# brain.net
KiCad netlist of a schematic drawn in EAGLE
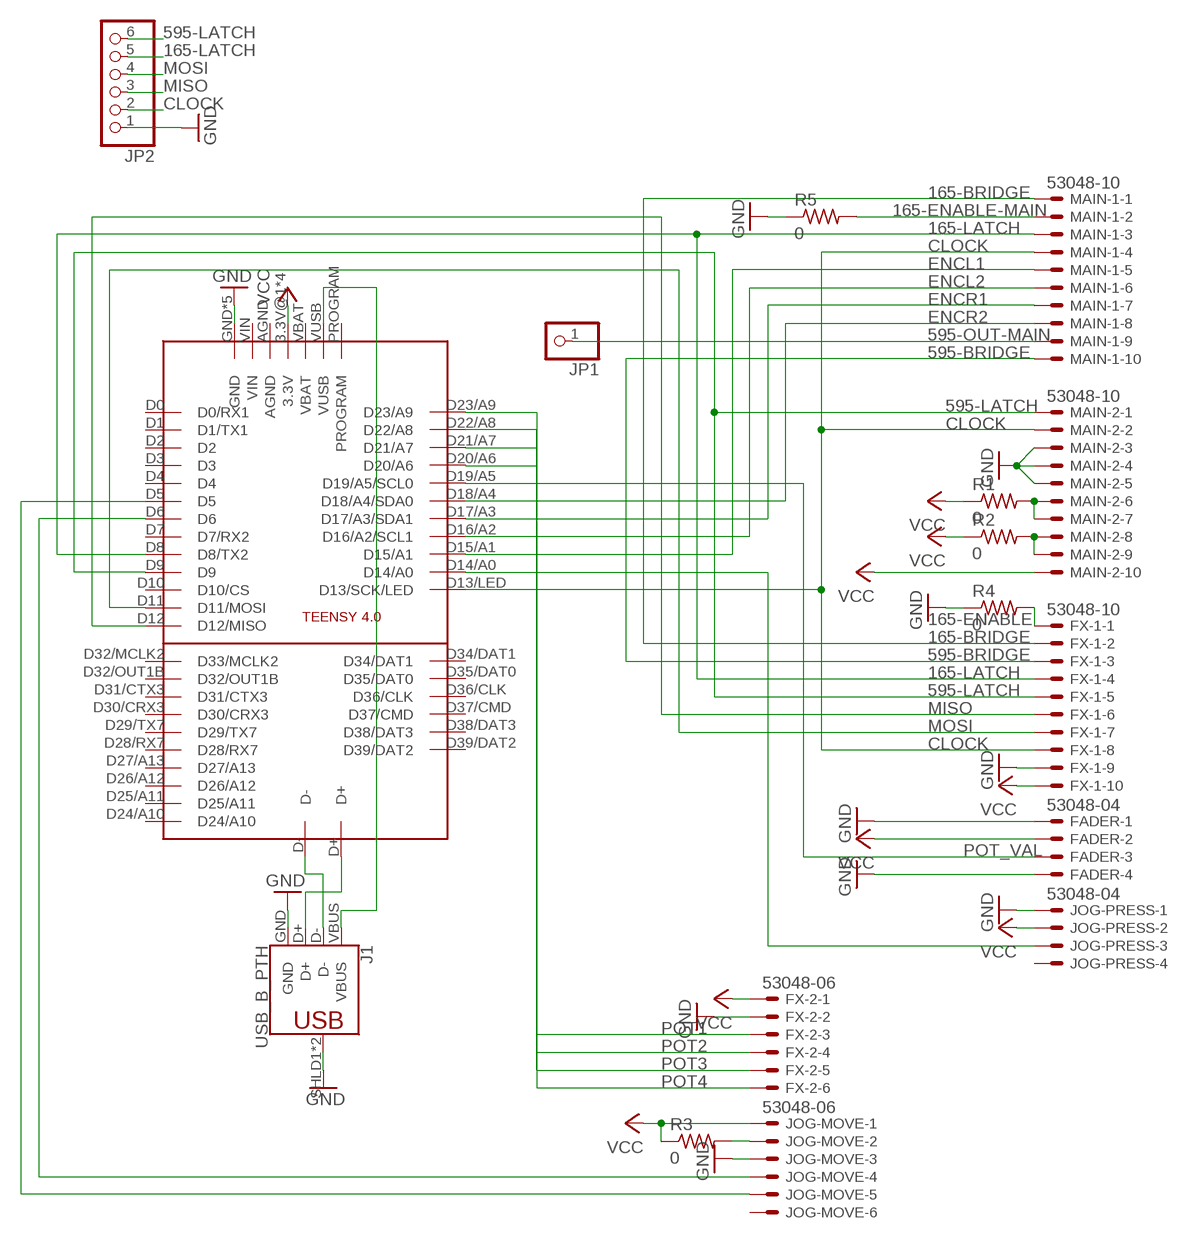
[diagram p0: schematic, sheet 1]

(export (version "E")
  (design (tool "Eeschema 10.0.6"))
  (components
    (comp (ref "FADER")
      (value "53048-04")
      (footprint "eagle-import:53048-04")
      (fields (field (name "MF") "MOLEX") (field (name "MPN") "53048-0410"))
      (libsource (lib "eagle-import") (part "53?-04048"))
    )
    (comp (ref "FX-1")
      (value "53048-10")
      (footprint "eagle-import:53048-10")
      (fields (field (name "MF") "MOLEX") (field (name "MPN") "53048-1010"))
      (libsource (lib "eagle-import") (part "53?-10048"))
    )
    (comp (ref "FX-2")
      (value "53048-06")
      (footprint "eagle-import:53048-06")
      (fields (field (name "MF") "WALDOM/MOLEX") (field (name "MPN") "53048-0610"))
      (libsource (lib "eagle-import") (part "53?-06048"))
    )
    (comp (ref "J1")
      (value "USB_B_PTH")
      (footprint "eagle-import:USB-B-PTH")
      (libsource (lib "eagle-import") (part "USB_B_PTH"))
    )
    (comp (ref "JOG-MOVE")
      (value "53048-06")
      (footprint "eagle-import:53048-06")
      (fields (field (name "MF") "WALDOM/MOLEX") (field (name "MPN") "53048-0610"))
      (libsource (lib "eagle-import") (part "53?-06048"))
    )
    (comp (ref "JOG-PRESS")
      (value "53048-04")
      (footprint "eagle-import:53048-04")
      (fields (field (name "MF") "MOLEX") (field (name "MPN") "53048-0410"))
      (libsource (lib "eagle-import") (part "53?-04048"))
    )
    (comp (ref "JP1")
      (value "PINHD-1X1")
      (footprint "eagle-import:1X01")
      (libsource (lib "eagle-import") (part "PINHD-1X1"))
    )
    (comp (ref "JP2")
      (value "PINHD-1X6")
      (footprint "eagle-import:1X06")
      (libsource (lib "eagle-import") (part "PINHD-1X6"))
    )
    (comp (ref "MAIN-1")
      (value "53048-10")
      (footprint "eagle-import:53048-10")
      (fields (field (name "MF") "MOLEX") (field (name "MPN") "53048-1010"))
      (libsource (lib "eagle-import") (part "53?-10048"))
    )
    (comp (ref "MAIN-2")
      (value "53048-10")
      (footprint "eagle-import:53048-10")
      (fields (field (name "MF") "MOLEX") (field (name "MPN") "53048-1010"))
      (libsource (lib "eagle-import") (part "53?-10048"))
    )
    (comp (ref "R1")
      (value "0")
      (footprint "eagle-import:R1206")
      (libsource (lib "eagle-import") (part "R-US_R1206"))
    )
    (comp (ref "R2")
      (value "0")
      (footprint "eagle-import:R1206")
      (libsource (lib "eagle-import") (part "R-US_R1206"))
    )
    (comp (ref "R3")
      (value "0")
      (footprint "eagle-import:R1206")
      (libsource (lib "eagle-import") (part "R-US_R1206"))
    )
    (comp (ref "R4")
      (value "0")
      (footprint "eagle-import:R1206")
      (libsource (lib "eagle-import") (part "R-US_R1206"))
    )
    (comp (ref "R5")
      (value "0")
      (footprint "eagle-import:R1206")
      (libsource (lib "eagle-import") (part "R-US_R1206"))
    )
    (comp (ref "U$1")
      (value "TEENSY-4.0-FULL-BRAKE-PADS")
      (footprint "eagle-import:TEENSY-4.0-FULL-BRAKE-PADS")
      (libsource (lib "eagle-import") (part "TEENSY-4.0-FULL-BRAKE-PADS"))
    )
  )
  (nets
    (net (code "1") (name "/165-BRIDGE") (class "Default")
      (node (ref "FX-1") (pin "2") (pinfunction "S_2") (pintype "passive"))
      (node (ref "MAIN-1") (pin "1") (pinfunction "S_1") (pintype "passive"))
    )
    (net (code "2") (name "/165-ENABLE") (class "Default")
      (node (ref "FX-1") (pin "1") (pinfunction "S_1") (pintype "passive"))
      (node (ref "R4") (pin "2") (pinfunction "2_2") (pintype "passive"))
    )
    (net (code "3") (name "/165-ENABLE-MAIN") (class "Default")
      (node (ref "MAIN-1") (pin "2") (pinfunction "S_2") (pintype "passive"))
      (node (ref "R5") (pin "2") (pinfunction "2_2") (pintype "passive"))
    )
    (net (code "4") (name "/165-LATCH") (class "Default")
      (node (ref "FX-1") (pin "4") (pinfunction "S_4") (pintype "passive"))
      (node (ref "JP2") (pin "5") (pinfunction "5_5") (pintype "passive"))
      (node (ref "MAIN-1") (pin "3") (pinfunction "S_3") (pintype "passive"))
      (node (ref "U$1") (pin "D8") (pinfunction "D8/TX2_D8") (pintype "bidirectional"))
    )
    (net (code "5") (name "/595-BRIDGE") (class "Default")
      (node (ref "FX-1") (pin "3") (pinfunction "S_3") (pintype "passive"))
      (node (ref "MAIN-1") (pin "10") (pinfunction "S_10") (pintype "passive"))
    )
    (net (code "6") (name "/595-LATCH") (class "Default")
      (node (ref "FX-1") (pin "5") (pinfunction "S_5") (pintype "passive"))
      (node (ref "JP2") (pin "6") (pinfunction "6_6") (pintype "passive"))
      (node (ref "MAIN-2") (pin "1") (pinfunction "S_1") (pintype "passive"))
      (node (ref "U$1") (pin "D9") (pinfunction "D9_D9") (pintype "bidirectional"))
    )
    (net (code "7") (name "/595-OUT-MAIN") (class "Default")
      (node (ref "JP1") (pin "1") (pinfunction "1_1") (pintype "passive"))
      (node (ref "MAIN-1") (pin "9") (pinfunction "S_9") (pintype "passive"))
    )
    (net (code "8") (name "/CLOCK") (class "Default")
      (node (ref "FX-1") (pin "8") (pinfunction "S_8") (pintype "passive"))
      (node (ref "JP2") (pin "2") (pinfunction "2_2") (pintype "passive"))
      (node (ref "MAIN-1") (pin "4") (pinfunction "S_4") (pintype "passive"))
      (node (ref "MAIN-2") (pin "2") (pinfunction "S_2") (pintype "passive"))
      (node (ref "U$1") (pin "D13/LED") (pinfunction "D13/SCK/LED_D13/LED") (pintype "bidirectional"))
    )
    (net (code "9") (name "/ENCL1") (class "Default")
      (node (ref "MAIN-1") (pin "5") (pinfunction "S_5") (pintype "passive"))
      (node (ref "U$1") (pin "D15/A1") (pinfunction "D15/A1_D15/A1") (pintype "bidirectional"))
    )
    (net (code "10") (name "/ENCL2") (class "Default")
      (node (ref "MAIN-1") (pin "6") (pinfunction "S_6") (pintype "passive"))
      (node (ref "U$1") (pin "D16/A2") (pinfunction "D16/A2/SCL1_D16/A2") (pintype "bidirectional"))
    )
    (net (code "11") (name "/ENCR1") (class "Default")
      (node (ref "MAIN-1") (pin "7") (pinfunction "S_7") (pintype "passive"))
      (node (ref "U$1") (pin "D17/A3") (pinfunction "D17/A3/SDA1_D17/A3") (pintype "bidirectional"))
    )
    (net (code "12") (name "/ENCR2") (class "Default")
      (node (ref "MAIN-1") (pin "8") (pinfunction "S_8") (pintype "passive"))
      (node (ref "U$1") (pin "D18/A4") (pinfunction "D18/A4/SDA0_D18/A4") (pintype "bidirectional"))
    )
    (net (code "13") (name "/MISO") (class "Default")
      (node (ref "FX-1") (pin "6") (pinfunction "S_6") (pintype "passive"))
      (node (ref "JP2") (pin "3") (pinfunction "3_3") (pintype "passive"))
      (node (ref "U$1") (pin "D12") (pinfunction "D12/MISO_D12") (pintype "bidirectional"))
    )
    (net (code "14") (name "/MOSI") (class "Default")
      (node (ref "FX-1") (pin "7") (pinfunction "S_7") (pintype "passive"))
      (node (ref "JP2") (pin "4") (pinfunction "4_4") (pintype "passive"))
      (node (ref "U$1") (pin "D11") (pinfunction "D11/MOSI_D11") (pintype "bidirectional"))
    )
    (net (code "15") (name "/POT1") (class "Default")
      (node (ref "FX-2") (pin "3") (pinfunction "S_3") (pintype "passive"))
      (node (ref "U$1") (pin "D20/A6") (pinfunction "D20/A6_D20/A6") (pintype "bidirectional"))
    )
    (net (code "16") (name "/POT2") (class "Default")
      (node (ref "FX-2") (pin "4") (pinfunction "S_4") (pintype "passive"))
      (node (ref "U$1") (pin "D21/A7") (pinfunction "D21/A7_D21/A7") (pintype "bidirectional"))
    )
    (net (code "17") (name "/POT3") (class "Default")
      (node (ref "FX-2") (pin "5") (pinfunction "S_5") (pintype "passive"))
      (node (ref "U$1") (pin "D22/A8") (pinfunction "D22/A8_D22/A8") (pintype "bidirectional"))
    )
    (net (code "18") (name "/POT4") (class "Default")
      (node (ref "FX-2") (pin "6") (pinfunction "S_6") (pintype "passive"))
      (node (ref "U$1") (pin "D23/A9") (pinfunction "D23/A9_D23/A9") (pintype "bidirectional"))
    )
    (net (code "19") (name "/POT_VAL") (class "Default")
      (node (ref "FADER") (pin "3") (pinfunction "S_3") (pintype "passive"))
      (node (ref "U$1") (pin "D19/A5") (pinfunction "D19/A5/SCL0_D19/A5") (pintype "bidirectional"))
    )
    (net (code "20") (name "GND") (class "Default")
      (node (ref "FADER") (pin "1") (pinfunction "S_1") (pintype "passive"))
      (node (ref "FADER") (pin "4") (pinfunction "S_4") (pintype "passive"))
      (node (ref "FX-1") (pin "9") (pinfunction "S_9") (pintype "passive"))
      (node (ref "FX-2") (pin "2") (pinfunction "S_2") (pintype "passive"))
      (node (ref "J1") (pin "GND") (pinfunction "GND_GND") (pintype "power_in"))
      (node (ref "J1") (pin "SHLD1") (pinfunction "SHIELD_SHLD1") (pintype "bidirectional"))
      (node (ref "J1") (pin "SHLD2") (pinfunction "SHIELD_SHLD2") (pintype "bidirectional"))
      (node (ref "JOG-MOVE") (pin "3") (pinfunction "S_3") (pintype "passive"))
      (node (ref "JOG-PRESS") (pin "1") (pinfunction "S_1") (pintype "passive"))
      (node (ref "JP2") (pin "1") (pinfunction "1_1") (pintype "passive"))
      (node (ref "MAIN-2") (pin "3") (pinfunction "S_3") (pintype "passive"))
      (node (ref "MAIN-2") (pin "4") (pinfunction "S_4") (pintype "passive"))
      (node (ref "MAIN-2") (pin "5") (pinfunction "S_5") (pintype "passive"))
      (node (ref "R4") (pin "1") (pinfunction "1_1") (pintype "passive"))
      (node (ref "R5") (pin "1") (pinfunction "1_1") (pintype "passive"))
      (node (ref "U$1") (pin "GND") (pinfunction "GND_GND") (pintype "bidirectional"))
      (node (ref "U$1") (pin "GND@1") (pinfunction "GND_GND@1") (pintype "bidirectional"))
      (node (ref "U$1") (pin "GND@2") (pinfunction "GND_GND@2") (pintype "bidirectional"))
      (node (ref "U$1") (pin "P$11") (pinfunction "GND_P$11") (pintype "bidirectional"))
      (node (ref "U$1") (pin "P$12") (pinfunction "GND_P$12") (pintype "bidirectional"))
    )
    (net (code "21") (name "Net-(J1-PadD+)") (class "Default")
      (node (ref "J1") (pin "D+") (pinfunction "D+_D+") (pintype "bidirectional"))
      (node (ref "U$1") (pin "D+") (pinfunction "D+_D+") (pintype "bidirectional"))
    )
    (net (code "22") (name "Net-(J1-PadD-)") (class "Default")
      (node (ref "J1") (pin "D-") (pinfunction "D-_D-") (pintype "bidirectional"))
      (node (ref "U$1") (pin "D-") (pinfunction "D-_D-") (pintype "bidirectional"))
    )
    (net (code "23") (name "Net-(J1-PadVBUS)") (class "Default")
      (node (ref "J1") (pin "VBUS") (pinfunction "VBUS_VBUS") (pintype "power_in"))
      (node (ref "U$1") (pin "VUSB") (pinfunction "VUSB_VUSB") (pintype "bidirectional"))
    )
    (net (code "24") (name "Net-(JOG-MOVEB-S)") (class "Default")
      (node (ref "JOG-MOVE") (pin "2") (pinfunction "S_2") (pintype "passive"))
      (node (ref "R3") (pin "2") (pinfunction "2_2") (pintype "passive"))
    )
    (net (code "25") (name "Net-(JOG-MOVED-S)") (class "Default")
      (node (ref "JOG-MOVE") (pin "4") (pinfunction "S_4") (pintype "passive"))
      (node (ref "U$1") (pin "D6") (pinfunction "D6_D6") (pintype "bidirectional"))
    )
    (net (code "26") (name "Net-(JOG-MOVEE-S)") (class "Default")
      (node (ref "JOG-MOVE") (pin "5") (pinfunction "S_5") (pintype "passive"))
      (node (ref "U$1") (pin "D5") (pinfunction "D5_D5") (pintype "bidirectional"))
    )
    (net (code "27") (name "Net-(JOG-PRESSC-S)") (class "Default")
      (node (ref "JOG-PRESS") (pin "3") (pinfunction "S_3") (pintype "passive"))
      (node (ref "U$1") (pin "D14/A0") (pinfunction "D14/A0_D14/A0") (pintype "bidirectional"))
    )
    (net (code "28") (name "Net-(MAIN-2G-S)") (class "Default")
      (node (ref "MAIN-2") (pin "6") (pinfunction "S_6") (pintype "passive"))
      (node (ref "MAIN-2") (pin "7") (pinfunction "S_7") (pintype "passive"))
      (node (ref "R1") (pin "2") (pinfunction "2_2") (pintype "passive"))
    )
    (net (code "29") (name "Net-(MAIN-2I-S)") (class "Default")
      (node (ref "MAIN-2") (pin "8") (pinfunction "S_8") (pintype "passive"))
      (node (ref "MAIN-2") (pin "9") (pinfunction "S_9") (pintype "passive"))
      (node (ref "R2") (pin "2") (pinfunction "2_2") (pintype "passive"))
    )
    (net (code "30") (name "VCC") (class "Default")
      (node (ref "FADER") (pin "2") (pinfunction "S_2") (pintype "passive"))
      (node (ref "FX-1") (pin "10") (pinfunction "S_10") (pintype "passive"))
      (node (ref "FX-2") (pin "1") (pinfunction "S_1") (pintype "passive"))
      (node (ref "JOG-MOVE") (pin "1") (pinfunction "S_1") (pintype "passive"))
      (node (ref "JOG-PRESS") (pin "2") (pinfunction "S_2") (pintype "passive"))
      (node (ref "MAIN-2") (pin "10") (pinfunction "S_10") (pintype "passive"))
      (node (ref "R1") (pin "1") (pinfunction "1_1") (pintype "passive"))
      (node (ref "R2") (pin "1") (pinfunction "1_1") (pintype "passive"))
      (node (ref "R3") (pin "1") (pinfunction "1_1") (pintype "passive"))
      (node (ref "U$1") (pin "3.3V@1") (pinfunction "3.3V_3.3V@1") (pintype "bidirectional"))
      (node (ref "U$1") (pin "3.3V@2") (pinfunction "3.3V_3.3V@2") (pintype "bidirectional"))
      (node (ref "U$1") (pin "3V3") (pinfunction "3.3V_3V3") (pintype "bidirectional"))
      (node (ref "U$1") (pin "ON/OFF") (pinfunction "3.3V_ON/OFF") (pintype "bidirectional"))
    )
    (net (code "31") (name "unconnected-(JOG-MOVEF-S-Pad6)") (class "Default")
      (node (ref "JOG-MOVE") (pin "6") (pinfunction "S_6") (pintype "passive"))
    )
    (net (code "32") (name "unconnected-(JOG-PRESSD-S-Pad4)") (class "Default")
      (node (ref "JOG-PRESS") (pin "4") (pinfunction "S_4") (pintype "passive"))
    )
    (net (code "33") (name "unconnected-(U$1-D0{slash}RX1-PadD0)") (class "Default")
      (node (ref "U$1") (pin "D0") (pinfunction "D0/RX1_D0") (pintype "bidirectional"))
    )
    (net (code "34") (name "unconnected-(U$1-D1{slash}TX1-PadD1)") (class "Default")
      (node (ref "U$1") (pin "D1") (pinfunction "D1/TX1_D1") (pintype "bidirectional"))
    )
    (net (code "35") (name "unconnected-(U$1-D7{slash}RX2-PadD7)") (class "Default")
      (node (ref "U$1") (pin "D7") (pinfunction "D7/RX2_D7") (pintype "bidirectional"))
    )
    (net (code "36") (name "unconnected-(U$1-D10{slash}CS-PadD10)") (class "Default")
      (node (ref "U$1") (pin "D10") (pinfunction "D10/CS_D10") (pintype "bidirectional"))
    )
    (net (code "37") (name "unconnected-(U$1-D33{slash}MCLK2-PadD32{slash}MCLK2)") (class "Default")
      (node (ref "U$1") (pin "D32/MCLK2") (pinfunction "D33/MCLK2_D32/MCLK2") (pintype "bidirectional"))
    )
    (net (code "38") (name "unconnected-(U$1-PadAGND)") (class "Default")
      (node (ref "U$1") (pin "AGND") (pinfunction "AGND_AGND") (pintype "bidirectional"))
    )
    (net (code "39") (name "unconnected-(U$1-PadD2)") (class "Default")
      (node (ref "U$1") (pin "D2") (pinfunction "D2_D2") (pintype "bidirectional"))
    )
    (net (code "40") (name "unconnected-(U$1-PadD3)") (class "Default")
      (node (ref "U$1") (pin "D3") (pinfunction "D3_D3") (pintype "bidirectional"))
    )
    (net (code "41") (name "unconnected-(U$1-PadD4)") (class "Default")
      (node (ref "U$1") (pin "D4") (pinfunction "D4_D4") (pintype "bidirectional"))
    )
    (net (code "42") (name "unconnected-(U$1-PadD24{slash}A10)") (class "Default")
      (node (ref "U$1") (pin "D24/A10") (pinfunction "D24/A10_D24/A10") (pintype "bidirectional"))
    )
    (net (code "43") (name "unconnected-(U$1-PadD25{slash}A11)") (class "Default")
      (node (ref "U$1") (pin "D25/A11") (pinfunction "D25/A11_D25/A11") (pintype "bidirectional"))
    )
    (net (code "44") (name "unconnected-(U$1-PadD26{slash}A12)") (class "Default")
      (node (ref "U$1") (pin "D26/A12") (pinfunction "D26/A12_D26/A12") (pintype "bidirectional"))
    )
    (net (code "45") (name "unconnected-(U$1-PadD27{slash}A13)") (class "Default")
      (node (ref "U$1") (pin "D27/A13") (pinfunction "D27/A13_D27/A13") (pintype "bidirectional"))
    )
    (net (code "46") (name "unconnected-(U$1-PadD28{slash}RX7)") (class "Default")
      (node (ref "U$1") (pin "D28/RX7") (pinfunction "D28/RX7_D28/RX7") (pintype "bidirectional"))
    )
    (net (code "47") (name "unconnected-(U$1-PadD29{slash}TX7)") (class "Default")
      (node (ref "U$1") (pin "D29/TX7") (pinfunction "D29/TX7_D29/TX7") (pintype "bidirectional"))
    )
    (net (code "48") (name "unconnected-(U$1-PadD30{slash}CRX3)") (class "Default")
      (node (ref "U$1") (pin "D30/CRX3") (pinfunction "D30/CRX3_D30/CRX3") (pintype "bidirectional"))
    )
    (net (code "49") (name "unconnected-(U$1-PadD31{slash}CTX3)") (class "Default")
      (node (ref "U$1") (pin "D31/CTX3") (pinfunction "D31/CTX3_D31/CTX3") (pintype "bidirectional"))
    )
    (net (code "50") (name "unconnected-(U$1-PadD32{slash}OUT1B)") (class "Default")
      (node (ref "U$1") (pin "D32/OUT1B") (pinfunction "D32/OUT1B_D32/OUT1B") (pintype "bidirectional"))
    )
    (net (code "51") (name "unconnected-(U$1-PadD34{slash}DAT1)") (class "Default")
      (node (ref "U$1") (pin "D34/DAT1") (pinfunction "D34/DAT1_D34/DAT1") (pintype "bidirectional"))
    )
    (net (code "52") (name "unconnected-(U$1-PadD35{slash}DAT0)") (class "Default")
      (node (ref "U$1") (pin "D35/DAT0") (pinfunction "D35/DAT0_D35/DAT0") (pintype "bidirectional"))
    )
    (net (code "53") (name "unconnected-(U$1-PadD36{slash}CLK)") (class "Default")
      (node (ref "U$1") (pin "D36/CLK") (pinfunction "D36/CLK_D36/CLK") (pintype "bidirectional"))
    )
    (net (code "54") (name "unconnected-(U$1-PadD37{slash}CMD)") (class "Default")
      (node (ref "U$1") (pin "D37/CMD") (pinfunction "D37/CMD_D37/CMD") (pintype "bidirectional"))
    )
    (net (code "55") (name "unconnected-(U$1-PadD38{slash}DAT3)") (class "Default")
      (node (ref "U$1") (pin "D38/DAT3") (pinfunction "D38/DAT3_D38/DAT3") (pintype "bidirectional"))
    )
    (net (code "56") (name "unconnected-(U$1-PadD39{slash}DAT2)") (class "Default")
      (node (ref "U$1") (pin "D39/DAT2") (pinfunction "D39/DAT2_D39/DAT2") (pintype "bidirectional"))
    )
    (net (code "57") (name "unconnected-(U$1-PadPROGRAM)") (class "Default")
      (node (ref "U$1") (pin "PROGRAM") (pinfunction "PROGRAM_PROGRAM") (pintype "bidirectional"))
    )
    (net (code "58") (name "unconnected-(U$1-PadVBAT)") (class "Default")
      (node (ref "U$1") (pin "VBAT") (pinfunction "VBAT_VBAT") (pintype "bidirectional"))
    )
    (net (code "59") (name "unconnected-(U$1-PadVIN)") (class "Default")
      (node (ref "U$1") (pin "VIN") (pinfunction "VIN_VIN") (pintype "bidirectional"))
    )
  )
)
